# harp_expander_servo_driver_v1_2.net
KiCad netlist of a schematic drawn in EAGLE
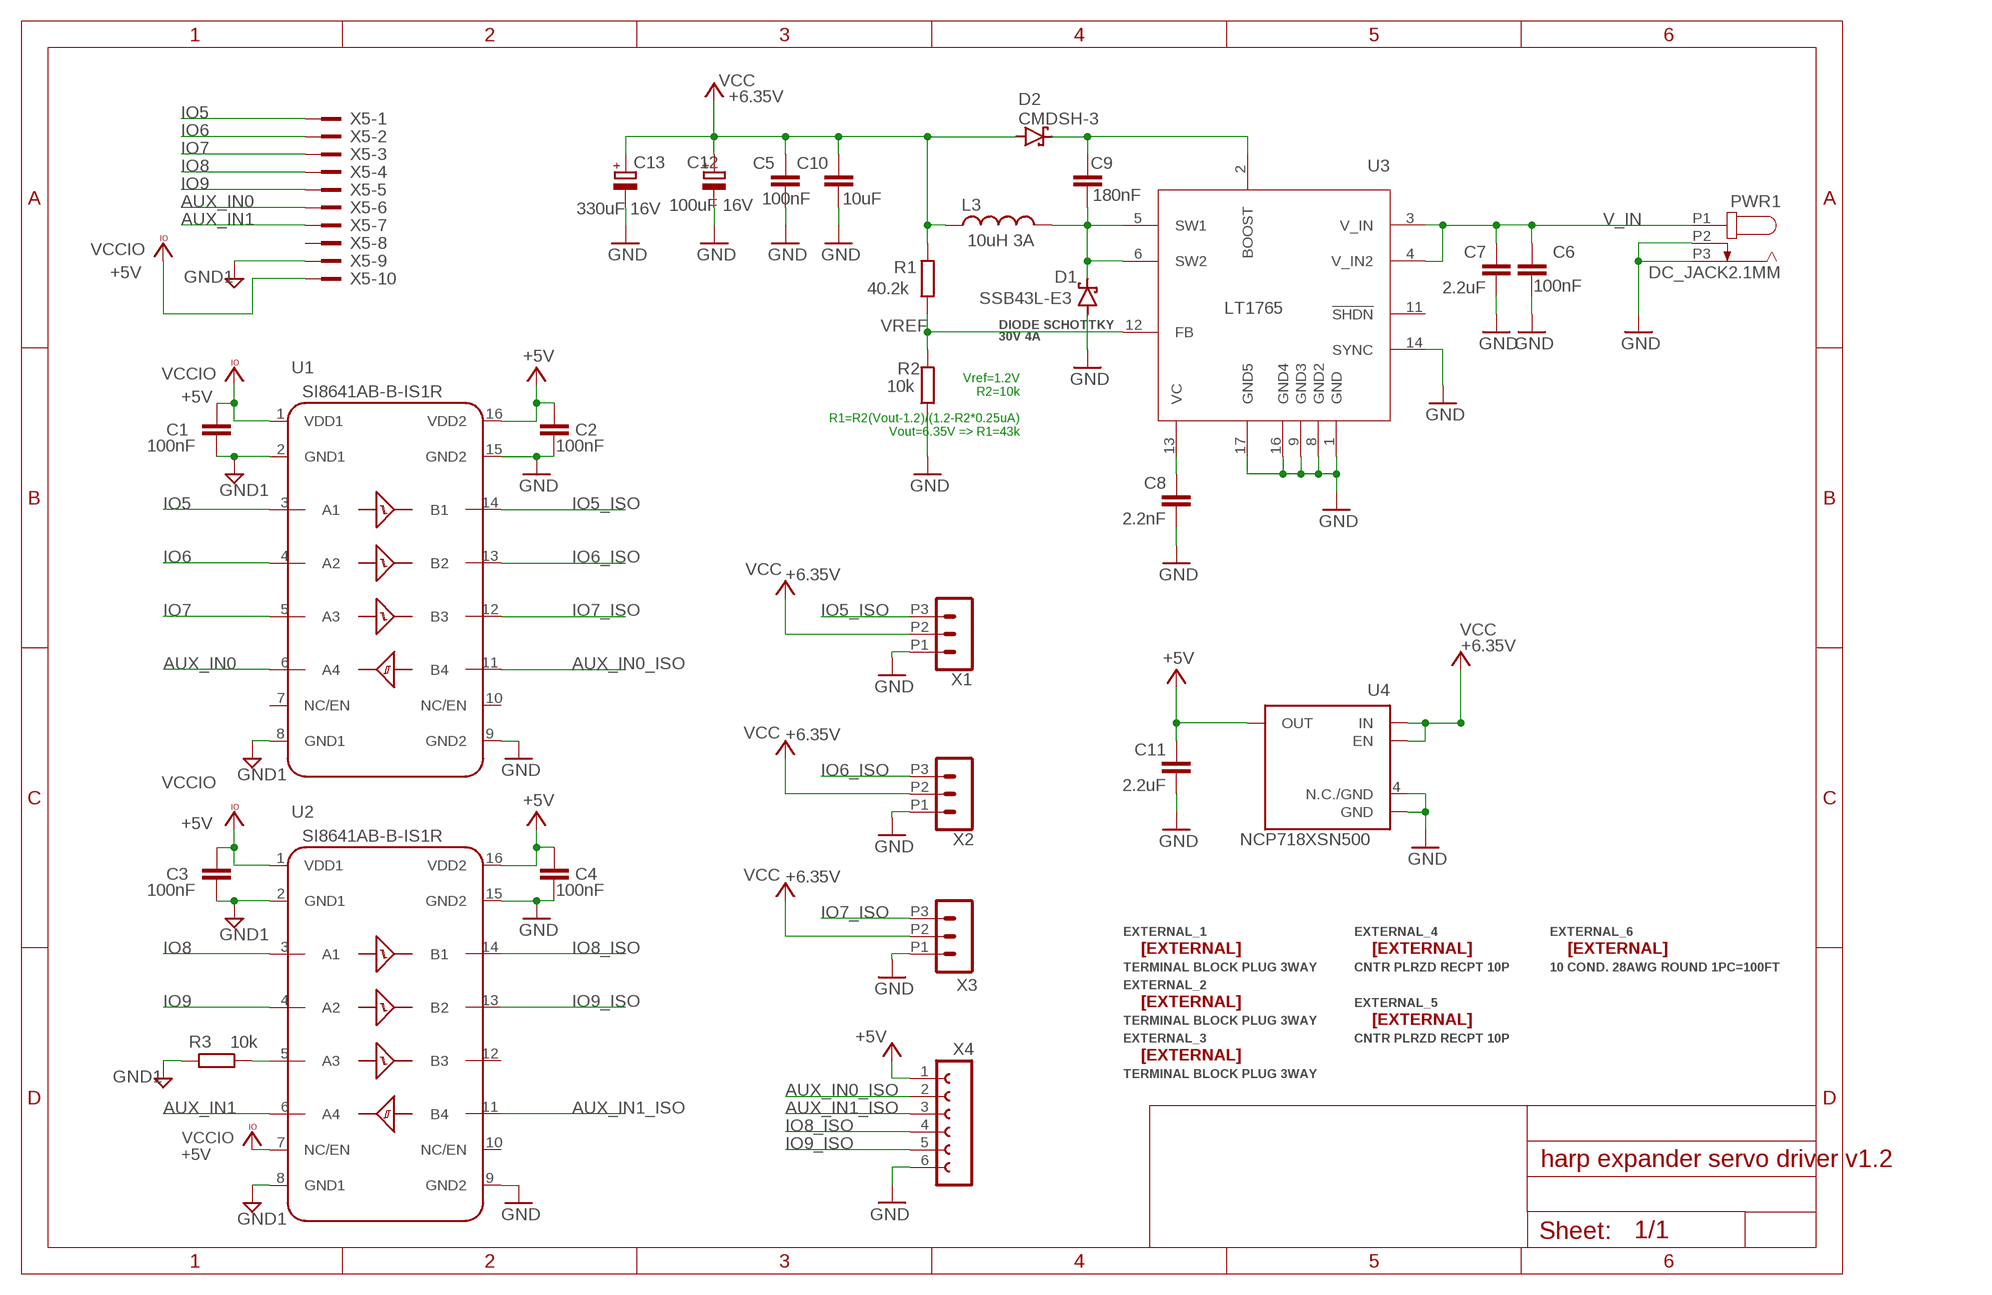
[diagram p0: schematic, sheet 1]

(export (version "E")
  (design (tool "Eeschema 10.0.6"))
  (components
    (comp (ref "C1")
      (value "100nF")
      (footprint "eagle-import:C0402")
      (fields (field (name "MPN") "CGA2B3X7R1H104K050BB"))
      (libsource (lib "eagle-import") (part "C-EUC0402"))
    )
    (comp (ref "C2")
      (value "100nF")
      (footprint "eagle-import:C0402")
      (fields (field (name "MPN") "CGA2B3X7R1H104K050BB"))
      (libsource (lib "eagle-import") (part "C-EUC0402"))
    )
    (comp (ref "C3")
      (value "100nF")
      (footprint "eagle-import:C0402")
      (fields (field (name "MPN") "CGA2B3X7R1H104K050BB"))
      (libsource (lib "eagle-import") (part "C-EUC0402"))
    )
    (comp (ref "C4")
      (value "100nF")
      (footprint "eagle-import:C0402")
      (fields (field (name "MPN") "CGA2B3X7R1H104K050BB"))
      (libsource (lib "eagle-import") (part "C-EUC0402"))
    )
    (comp (ref "C5")
      (value "100nF")
      (footprint "eagle-import:C0402")
      (fields (field (name "MPN") "CGA2B3X7R1H104K050BB"))
      (libsource (lib "eagle-import") (part "C-EUC0402"))
    )
    (comp (ref "C6")
      (value "100nF")
      (footprint "eagle-import:C0402")
      (fields (field (name "MPN") "CGA2B3X7R1H104K050BB"))
      (libsource (lib "eagle-import") (part "C-EUC0402"))
    )
    (comp (ref "C7")
      (value "2.2uF")
      (footprint "eagle-import:C0603")
      (fields (field (name "MPN") "GRM188R61E225MA12D"))
      (libsource (lib "eagle-import") (part "C-EUC0603"))
    )
    (comp (ref "C8")
      (value "2.2nF")
      (footprint "eagle-import:C0402")
      (fields (field (name "MPN") "CL05B222JB5NNNC"))
      (libsource (lib "eagle-import") (part "C-EUC0402"))
    )
    (comp (ref "C9")
      (value "180nF")
      (footprint "eagle-import:C0603")
      (fields (field (name "MPN") "GCG188R91H184KA01D"))
      (libsource (lib "eagle-import") (part "C-EUC0603"))
    )
    (comp (ref "C10")
      (value "10uF")
      (footprint "eagle-import:C0603")
      (fields (field (name "MPN") "EMK107BBJ106MA-T"))
      (libsource (lib "eagle-import") (part "C-EUC0603"))
    )
    (comp (ref "C11")
      (value "2.2uF")
      (footprint "eagle-import:C0603")
      (fields (field (name "MPN") "GRM188R61E225MA12D"))
      (libsource (lib "eagle-import") (part "C-EUC0603"))
    )
    (comp (ref "C12")
      (value "100uF 16V")
      (footprint "eagle-import:CT7343")
      (fields (field (name "MPN") "T491D107K016AT7280"))
      (libsource (lib "eagle-import") (part "CPOL-EUCT7343"))
    )
    (comp (ref "C13")
      (value "330uF 16V")
      (footprint "eagle-import:E3,5-8")
      (fields (field (name "MPN") "MCMR16V337M8X7"))
      (libsource (lib "eagle-import") (part "CPOL-EUE3.5-8"))
    )
    (comp (ref "D1")
      (value "SSB43L-E3")
      (footprint "eagle-import:SMB")
      (fields (field (name "MPN") "SSB43L-E3/52T"))
      (libsource (lib "eagle-import") (part "MBRS130LT3"))
    )
    (comp (ref "D2")
      (value "CMDSH-3")
      (footprint "eagle-import:SOD323-R")
      (libsource (lib "eagle-import") (part "SCHOTTKY-DIODESOD323"))
    )
    (comp (ref "EXTERNAL_1")
      (value "TERMINAL BLOCK PLUG 3WAY")
      (footprint "eagle-import:-")
      (fields (field (name "MPN") "691361100003") (field (name "TYPE") "-"))
      (libsource (lib "eagle-import") (part "EXTERNAL"))
    )
    (comp (ref "EXTERNAL_2")
      (value "TERMINAL BLOCK PLUG 3WAY")
      (footprint "eagle-import:-")
      (fields (field (name "MPN") "691361100003") (field (name "TYPE") "-"))
      (libsource (lib "eagle-import") (part "EXTERNAL"))
    )
    (comp (ref "EXTERNAL_3")
      (value "TERMINAL BLOCK PLUG 3WAY")
      (footprint "eagle-import:-")
      (fields (field (name "MPN") "691361100003") (field (name "TYPE") "-"))
      (libsource (lib "eagle-import") (part "EXTERNAL"))
    )
    (comp (ref "EXTERNAL_4")
      (value "CNTR PLRZD RECPT 10P")
      (footprint "eagle-import:-")
      (fields (field (name "MPN") "1658621-1") (field (name "TYPE") "-"))
      (libsource (lib "eagle-import") (part "EXTERNAL"))
    )
    (comp (ref "EXTERNAL_5")
      (value "CNTR PLRZD RECPT 10P")
      (footprint "eagle-import:-")
      (fields (field (name "MPN") "1658621-1") (field (name "TYPE") "-"))
      (libsource (lib "eagle-import") (part "EXTERNAL"))
    )
    (comp (ref "EXTERNAL_6")
      (value "10 COND. 28AWG ROUND 1PC=100FT")
      (footprint "eagle-import:-")
      (fields (field (name "MPN") "3365/10 100") (field (name "TYPE") "-"))
      (libsource (lib "eagle-import") (part "EXTERNAL"))
    )
    (comp (ref "L3")
      (value "10uH 3A")
      (footprint "eagle-import:L_IHLP_PADS")
      (fields (field (name "MPN") "IHLP2525CZER100M01"))
      (libsource (lib "eagle-import") (part "L_IHLP2525CZER100M01"))
    )
    (comp (ref "PWR1")
      (value "DC_JACK2.1MM")
      (footprint "eagle-import:DC_POWER_INPUT_2.1MM")
      (fields (field (name "MPN") "163-179PH-EX"))
      (libsource (lib "eagle-import") (part "DC_JACK2.1MM"))
    )
    (comp (ref "R1")
      (value "40.2k")
      (footprint "eagle-import:R0402")
      (fields (field (name "MPN") "RC0402FR-0740K2L"))
      (libsource (lib "eagle-import") (part "R-EU_R0402"))
    )
    (comp (ref "R2")
      (value "10k")
      (footprint "eagle-import:R0402")
      (fields (field (name "MPN") "CRCW040210K0FKEDC"))
      (libsource (lib "eagle-import") (part "R-EU_R0402"))
    )
    (comp (ref "R3")
      (value "10k")
      (footprint "eagle-import:R0402")
      (fields (field (name "MPN") "CRCW040210K0FKEDC"))
      (libsource (lib "eagle-import") (part "R-EU_R0402"))
    )
    (comp (ref "U1")
      (value "SI8641AB-B-IS1R")
      (footprint "eagle-import:SO16W")
      (libsource (lib "eagle-import") (part "SI8641ABW"))
    )
    (comp (ref "U2")
      (value "SI8641AB-B-IS1R")
      (footprint "eagle-import:SO16W")
      (libsource (lib "eagle-import") (part "SI8641ABW"))
    )
    (comp (ref "U3")
      (value "LT1765")
      (footprint "eagle-import:TSSOP16")
      (fields (field (name "MPN") "LT1765EFE#TRPBF"))
      (libsource (lib "eagle-import") (part "LT1765"))
    )
    (comp (ref "U4")
      (value "NCP718XSN500")
      (footprint "eagle-import:SOT23-5")
      (fields (field (name "MPN") "NCP718BSN500T1G"))
      (libsource (lib "eagle-import") (part "NCP718XSN500"))
    )
    (comp (ref "X1")
      (value "CON_3.5MM_1X3")
      (footprint "eagle-import:CON_3.5MM_1X3")
      (fields (field (name "MPN") "691322110003"))
      (libsource (lib "eagle-import") (part "CON_3.5MM_1X3"))
    )
    (comp (ref "X2")
      (value "CON_3.5MM_1X3")
      (footprint "eagle-import:CON_3.5MM_1X3")
      (fields (field (name "MPN") "691322110003"))
      (libsource (lib "eagle-import") (part "CON_3.5MM_1X3"))
    )
    (comp (ref "X3")
      (value "CON_3.5MM_1X3")
      (footprint "eagle-import:CON_3.5MM_1X3")
      (fields (field (name "MPN") "691322110003"))
      (libsource (lib "eagle-import") (part "CON_3.5MM_1X3"))
    )
    (comp (ref "X4")
      (value "aux_header")
      (footprint "eagle-import:FE06")
      (fields (field (name "MPN") "n.a."))
      (libsource (lib "eagle-import") (part "FE06-1"))
    )
    (comp (ref "X5")
      (value "IDC 10WAY STRAIGHT")
      (footprint "eagle-import:PAK100_2500-10")
      (fields
        (field (name "MF") "3M")
        (field (name "MPN") "2510-6002UB")
        (field (name "DIGIKEY_PN") "S9169-ND")
        (field (name "MF_1") "-")
        (field (name "MPN_1") "SBH11-PBPC-D05-ST-BK")
        (field (name "OC_FARNELL") "-")
        (field (name "OC_NEWARK") "-")
        (field (name "TYPE") "TH")
      )
      (libsource (lib "eagle-import") (part "2510-"))
    )
  )
  (nets
    (net (code "1") (name "+5V") (class "Default")
      (node (ref "C11") (pin "1") (pinfunction "1_1") (pintype "passive"))
      (node (ref "C2") (pin "1") (pinfunction "1_1") (pintype "passive"))
      (node (ref "C4") (pin "1") (pinfunction "1_1") (pintype "passive"))
      (node (ref "U1") (pin "16") (pinfunction "VDD2_16") (pintype "bidirectional"))
      (node (ref "U2") (pin "16") (pinfunction "VDD2_16") (pintype "bidirectional"))
      (node (ref "U4") (pin "5") (pinfunction "OUT_5") (pintype "passive"))
      (node (ref "X4") (pin "1") (pinfunction "1_1") (pintype "passive"))
    )
    (net (code "2") (name "/AUX_IN0") (class "Default")
      (node (ref "U1") (pin "6") (pinfunction "A4_6") (pintype "bidirectional"))
      (node (ref "X5") (pin "6") (pinfunction "KL_6") (pintype "passive"))
    )
    (net (code "3") (name "/AUX_IN0_ISO") (class "Default")
      (node (ref "U1") (pin "11") (pinfunction "B4_11") (pintype "bidirectional"))
      (node (ref "X4") (pin "2") (pinfunction "2_2") (pintype "passive"))
    )
    (net (code "4") (name "/AUX_IN1") (class "Default")
      (node (ref "U2") (pin "6") (pinfunction "A4_6") (pintype "bidirectional"))
      (node (ref "X5") (pin "7") (pinfunction "KL_7") (pintype "passive"))
    )
    (net (code "5") (name "/AUX_IN1_ISO") (class "Default")
      (node (ref "U2") (pin "11") (pinfunction "B4_11") (pintype "bidirectional"))
      (node (ref "X4") (pin "3") (pinfunction "3_3") (pintype "passive"))
    )
    (net (code "6") (name "/IO5") (class "Default")
      (node (ref "U1") (pin "3") (pinfunction "A1_3") (pintype "bidirectional"))
      (node (ref "X5") (pin "1") (pinfunction "KL_1") (pintype "passive"))
    )
    (net (code "7") (name "/IO5_ISO") (class "Default")
      (node (ref "U1") (pin "14") (pinfunction "B1_14") (pintype "bidirectional"))
      (node (ref "X1") (pin "P3") (pinfunction "3_P3") (pintype "passive"))
    )
    (net (code "8") (name "/IO6") (class "Default")
      (node (ref "U1") (pin "4") (pinfunction "A2_4") (pintype "bidirectional"))
      (node (ref "X5") (pin "2") (pinfunction "KL_2") (pintype "passive"))
    )
    (net (code "9") (name "/IO6_ISO") (class "Default")
      (node (ref "U1") (pin "13") (pinfunction "B2_13") (pintype "bidirectional"))
      (node (ref "X2") (pin "P3") (pinfunction "3_P3") (pintype "passive"))
    )
    (net (code "10") (name "/IO7") (class "Default")
      (node (ref "U1") (pin "5") (pinfunction "A3_5") (pintype "bidirectional"))
      (node (ref "X5") (pin "3") (pinfunction "KL_3") (pintype "passive"))
    )
    (net (code "11") (name "/IO7_ISO") (class "Default")
      (node (ref "U1") (pin "12") (pinfunction "B3_12") (pintype "bidirectional"))
      (node (ref "X3") (pin "P3") (pinfunction "3_P3") (pintype "passive"))
    )
    (net (code "12") (name "/IO8") (class "Default")
      (node (ref "U2") (pin "3") (pinfunction "A1_3") (pintype "bidirectional"))
      (node (ref "X5") (pin "4") (pinfunction "KL_4") (pintype "passive"))
    )
    (net (code "13") (name "/IO8_ISO") (class "Default")
      (node (ref "U2") (pin "14") (pinfunction "B1_14") (pintype "bidirectional"))
      (node (ref "X4") (pin "4") (pinfunction "4_4") (pintype "passive"))
    )
    (net (code "14") (name "/IO9") (class "Default")
      (node (ref "U2") (pin "4") (pinfunction "A2_4") (pintype "bidirectional"))
      (node (ref "X5") (pin "5") (pinfunction "KL_5") (pintype "passive"))
    )
    (net (code "15") (name "/IO9_ISO") (class "Default")
      (node (ref "U2") (pin "13") (pinfunction "B2_13") (pintype "bidirectional"))
      (node (ref "X4") (pin "5") (pinfunction "5_5") (pintype "passive"))
    )
    (net (code "16") (name "/VREF") (class "Default")
      (node (ref "R1") (pin "1") (pinfunction "1_1") (pintype "passive"))
      (node (ref "R2") (pin "2") (pinfunction "2_2") (pintype "passive"))
      (node (ref "U3") (pin "12") (pinfunction "FB_12") (pintype "passive"))
    )
    (net (code "17") (name "/V_IN") (class "Default")
      (node (ref "C6") (pin "1") (pinfunction "1_1") (pintype "passive"))
      (node (ref "C7") (pin "1") (pinfunction "1_1") (pintype "passive"))
      (node (ref "PWR1") (pin "P1") (pinfunction "1_P1") (pintype "passive"))
      (node (ref "U3") (pin "3") (pinfunction "V_IN_3") (pintype "passive"))
      (node (ref "U3") (pin "4") (pinfunction "V_IN2_4") (pintype "passive"))
    )
    (net (code "18") (name "GND") (class "Default")
      (node (ref "C10") (pin "2") (pinfunction "2_2") (pintype "passive"))
      (node (ref "C11") (pin "2") (pinfunction "2_2") (pintype "passive"))
      (node (ref "C12") (pin "-") (pinfunction "-_-") (pintype "passive"))
      (node (ref "C13") (pin "-") (pinfunction "-_-") (pintype "passive"))
      (node (ref "C2") (pin "2") (pinfunction "2_2") (pintype "passive"))
      (node (ref "C4") (pin "2") (pinfunction "2_2") (pintype "passive"))
      (node (ref "C5") (pin "2") (pinfunction "2_2") (pintype "passive"))
      (node (ref "C6") (pin "2") (pinfunction "2_2") (pintype "passive"))
      (node (ref "C7") (pin "2") (pinfunction "2_2") (pintype "passive"))
      (node (ref "C8") (pin "2") (pinfunction "2_2") (pintype "passive"))
      (node (ref "D1") (pin "A") (pinfunction "A_A") (pintype "passive"))
      (node (ref "PWR1") (pin "P2") (pinfunction "2_P2") (pintype "passive"))
      (node (ref "PWR1") (pin "P3") (pinfunction "3_P3") (pintype "passive"))
      (node (ref "R2") (pin "1") (pinfunction "1_1") (pintype "passive"))
      (node (ref "U1") (pin "15") (pinfunction "GND2_15") (pintype "bidirectional"))
      (node (ref "U1") (pin "9") (pinfunction "GND2_9") (pintype "bidirectional"))
      (node (ref "U2") (pin "15") (pinfunction "GND2_15") (pintype "bidirectional"))
      (node (ref "U2") (pin "9") (pinfunction "GND2_9") (pintype "bidirectional"))
      (node (ref "U3") (pin "1") (pinfunction "GND_1") (pintype "passive"))
      (node (ref "U3") (pin "14") (pinfunction "SYNC_14") (pintype "passive"))
      (node (ref "U3") (pin "16") (pinfunction "GND4_16") (pintype "passive"))
      (node (ref "U3") (pin "17") (pinfunction "GND5_17") (pintype "passive"))
      (node (ref "U3") (pin "8") (pinfunction "GND2_8") (pintype "passive"))
      (node (ref "U3") (pin "9") (pinfunction "GND3_9") (pintype "passive"))
      (node (ref "U4") (pin "2") (pinfunction "GND_2") (pintype "passive"))
      (node (ref "U4") (pin "4") (pinfunction "N.C./GND_4") (pintype "passive"))
      (node (ref "X1") (pin "P1") (pinfunction "1_P1") (pintype "passive"))
      (node (ref "X2") (pin "P1") (pinfunction "1_P1") (pintype "passive"))
      (node (ref "X3") (pin "P1") (pinfunction "1_P1") (pintype "passive"))
      (node (ref "X4") (pin "6") (pinfunction "6_6") (pintype "passive"))
    )
    (net (code "19") (name "GND1") (class "Default")
      (node (ref "C1") (pin "2") (pinfunction "2_2") (pintype "passive"))
      (node (ref "C3") (pin "2") (pinfunction "2_2") (pintype "passive"))
      (node (ref "R3") (pin "2") (pinfunction "2_2") (pintype "passive"))
      (node (ref "U1") (pin "2") (pinfunction "GND1_2") (pintype "bidirectional"))
      (node (ref "U1") (pin "8") (pinfunction "GND1_8") (pintype "bidirectional"))
      (node (ref "U2") (pin "2") (pinfunction "GND1_2") (pintype "bidirectional"))
      (node (ref "U2") (pin "8") (pinfunction "GND1_8") (pintype "bidirectional"))
      (node (ref "X5") (pin "9") (pinfunction "KL_9") (pintype "passive"))
    )
    (net (code "20") (name "Net-(U2-A3)") (class "Default")
      (node (ref "R3") (pin "1") (pinfunction "1_1") (pintype "passive"))
      (node (ref "U2") (pin "5") (pinfunction "A3_5") (pintype "bidirectional"))
    )
    (net (code "21") (name "Net-(U3-BOOST)") (class "Default")
      (node (ref "C9") (pin "1") (pinfunction "1_1") (pintype "passive"))
      (node (ref "D2") (pin "C") (pinfunction "C_C") (pintype "passive"))
      (node (ref "U3") (pin "2") (pinfunction "BOOST_2") (pintype "passive"))
    )
    (net (code "22") (name "Net-(U3-SW1)") (class "Default")
      (node (ref "C9") (pin "2") (pinfunction "2_2") (pintype "passive"))
      (node (ref "D1") (pin "C") (pinfunction "C_C") (pintype "passive"))
      (node (ref "L3") (pin "2") (pinfunction "2_2") (pintype "passive"))
      (node (ref "U3") (pin "5") (pinfunction "SW1_5") (pintype "passive"))
      (node (ref "U3") (pin "6") (pinfunction "SW2_6") (pintype "passive"))
    )
    (net (code "23") (name "Net-(U3-VC)") (class "Default")
      (node (ref "C8") (pin "1") (pinfunction "1_1") (pintype "passive"))
      (node (ref "U3") (pin "13") (pinfunction "VC_13") (pintype "passive"))
    )
    (net (code "24") (name "VCC") (class "Default")
      (node (ref "C10") (pin "1") (pinfunction "1_1") (pintype "passive"))
      (node (ref "C12") (pin "+") (pinfunction "+_+") (pintype "passive"))
      (node (ref "C13") (pin "+") (pinfunction "+_+") (pintype "passive"))
      (node (ref "C5") (pin "1") (pinfunction "1_1") (pintype "passive"))
      (node (ref "D2") (pin "A") (pinfunction "A_A") (pintype "passive"))
      (node (ref "L3") (pin "1") (pinfunction "1_1") (pintype "passive"))
      (node (ref "R1") (pin "2") (pinfunction "2_2") (pintype "passive"))
      (node (ref "U4") (pin "1") (pinfunction "IN_1") (pintype "passive"))
      (node (ref "U4") (pin "3") (pinfunction "EN_3") (pintype "passive"))
      (node (ref "X1") (pin "P2") (pinfunction "2_P2") (pintype "passive"))
      (node (ref "X2") (pin "P2") (pinfunction "2_P2") (pintype "passive"))
      (node (ref "X3") (pin "P2") (pinfunction "2_P2") (pintype "passive"))
    )
    (net (code "25") (name "VCCIO") (class "Default")
      (node (ref "C1") (pin "1") (pinfunction "1_1") (pintype "passive"))
      (node (ref "C3") (pin "1") (pinfunction "1_1") (pintype "passive"))
      (node (ref "U1") (pin "1") (pinfunction "VDD1_1") (pintype "bidirectional"))
      (node (ref "U2") (pin "1") (pinfunction "VDD1_1") (pintype "bidirectional"))
      (node (ref "U2") (pin "7") (pinfunction "NC/EN_7") (pintype "bidirectional"))
      (node (ref "X5") (pin "10") (pinfunction "KL_10") (pintype "passive"))
    )
    (net (code "26") (name "unconnected-(U1-NC{slash}EN-Pad7)") (class "Default")
      (node (ref "U1") (pin "7") (pinfunction "NC/EN_7") (pintype "bidirectional"))
    )
    (net (code "27") (name "unconnected-(U1-NC{slash}EN-Pad10)") (class "Default")
      (node (ref "U1") (pin "10") (pinfunction "NC/EN_10") (pintype "bidirectional"))
    )
    (net (code "28") (name "unconnected-(U2-B3-Pad12)") (class "Default")
      (node (ref "U2") (pin "12") (pinfunction "B3_12") (pintype "bidirectional"))
    )
    (net (code "29") (name "unconnected-(U2-NC{slash}EN-Pad10)") (class "Default")
      (node (ref "U2") (pin "10") (pinfunction "NC/EN_10") (pintype "bidirectional"))
    )
    (net (code "30") (name "unconnected-(U3-NC7-Pad7)") (class "Default")
      (node (ref "U3") (pin "7") (pinfunction "NC7_7") (pintype "no_connect"))
    )
    (net (code "31") (name "unconnected-(U3-NC10-Pad10)") (class "Default")
      (node (ref "U3") (pin "10") (pinfunction "NC10_10") (pintype "no_connect"))
    )
    (net (code "32") (name "unconnected-(U3-NC15-Pad15)") (class "Default")
      (node (ref "U3") (pin "15") (pinfunction "NC15_15") (pintype "no_connect"))
    )
    (net (code "33") (name "unconnected-(U3-~{SHDN}-Pad11)") (class "Default")
      (node (ref "U3") (pin "11") (pinfunction "~{SHDN}_11") (pintype "passive"))
    )
    (net (code "34") (name "unconnected-(X5I-KL-Pad8)") (class "Default")
      (node (ref "X5") (pin "8") (pinfunction "KL_8") (pintype "passive"))
    )
  )
)
